# SdpSchemRev1.net
KiCad netlist of a schematic drawn in Altium Designer
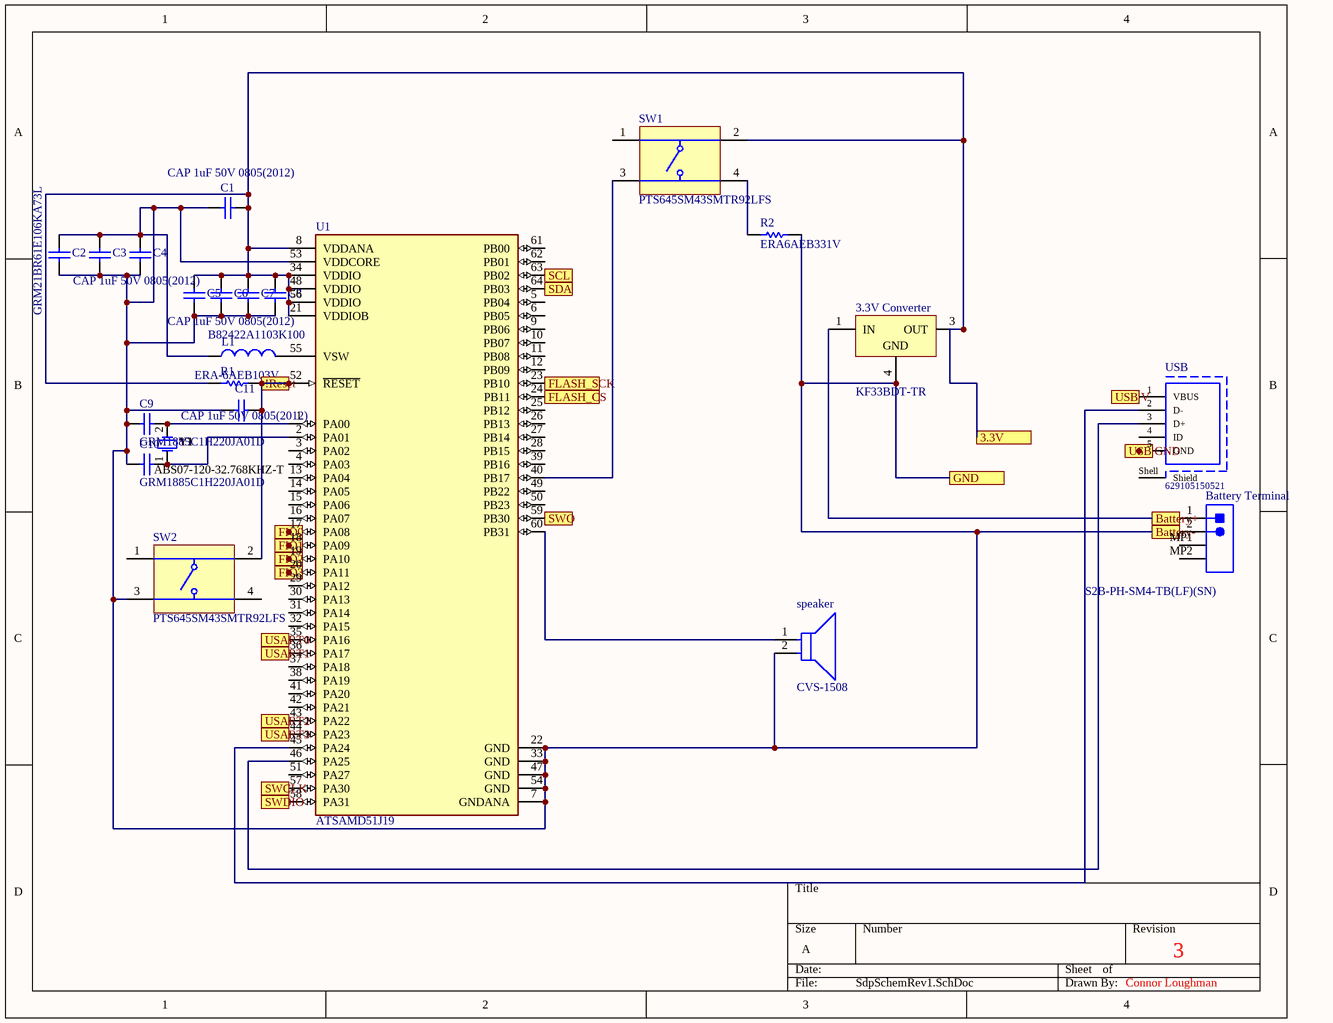
[diagram p0: SdpSchemRev1.SchDoc]

(export (version "E")
  (design (tool "Eeschema 10.0.6"))
  (components
    (comp (ref "3.3V Converter")
      (value "KF33BDT-TR")
      (footprint "TO-252_L")
      (description "Very Low Drop Voltage Regulators with Inhibit, 3.3V, 3-Pin DPAK, Tape and Reel")
      (libsource (lib "Altium Content Vault") (part "PM-REG-L4940-SOT3"))
    )
    (comp (ref "Battery Terminal")
      (value "S2B-PH-SM4-TB(LF)(SN)")
      (footprint "JST- S2B-PH-SM4-TB(LF)(SN)-2_V")
      (description "Male Header, Pitch 2 mm, 1 x 2 Position, Height 5.5 mm, -25 to 85 degC, RoHS, Tape and Reel")
      (libsource (lib "Altium Content Vault") (part "CN-1P-2M-R2"))
    )
    (comp (ref "C1")
      (value "CAP 1uF 50V 0805(2012)")
      (footprint "CAPC0805(2012)145_L")
      (description "CAP 1uF 50V ±10% 0805 (2012 Metric) Thickness 1.45mm SMD")
      (fields (field (name "TOLERANCE") "Â±10%"))
      (libsource (lib "Altium Content Vault") (part "CAP"))
    )
    (comp (ref "C2")
      (value "GRM21BR61E106KA73L")
      (footprint "CAPC2013X135X45ML10T25")
      (fields (field (name "MANUFACTURER") "Murata"))
      (libsource (lib "Altium Content Vault") (part "CAP"))
    )
    (comp (ref "C3")
      (value "~")
      (footprint "CAPC0805(2012)145_L")
      (description "CAP 1uF 50V ±10% 0805 (2012 Metric) Thickness 1.45mm SMD")
      (fields (field (name "TOLERANCE") "Â±10%"))
      (libsource (lib "Altium Content Vault") (part "CAP"))
    )
    (comp (ref "C4")
      (value "CAP 1uF 50V 0805(2012)")
      (footprint "CAPC0805(2012)145_L")
      (description "CAP 1uF 50V ±10% 0805 (2012 Metric) Thickness 1.45mm SMD")
      (fields (field (name "TOLERANCE") "Â±10%"))
      (libsource (lib "Altium Content Vault") (part "CAP"))
    )
    (comp (ref "C5")
      (value "~")
      (footprint "CAPC0805(2012)145_L")
      (description "CAP 1uF 50V ±10% 0805 (2012 Metric) Thickness 1.45mm SMD")
      (fields (field (name "TOLERANCE") "Â±10%"))
      (libsource (lib "Altium Content Vault") (part "CAP"))
    )
    (comp (ref "C6")
      (value "~")
      (footprint "CAPC0805(2012)145_L")
      (description "CAP 1uF 50V ±10% 0805 (2012 Metric) Thickness 1.45mm SMD")
      (fields (field (name "TOLERANCE") "Â±10%"))
      (libsource (lib "Altium Content Vault") (part "CAP"))
    )
    (comp (ref "C7")
      (value "~")
      (footprint "CAPC0805(2012)145_L")
      (description "CAP 1uF 50V ±10% 0805 (2012 Metric) Thickness 1.45mm SMD")
      (fields (field (name "TOLERANCE") "Â±10%"))
      (libsource (lib "Altium Content Vault") (part "CAP"))
    )
    (comp (ref "C8")
      (value "CAP 1uF 50V 0805(2012)")
      (footprint "CAPC0805(2012)145_L")
      (description "CAP 1uF 50V ±10% 0805 (2012 Metric) Thickness 1.45mm SMD")
      (fields (field (name "TOLERANCE") "Â±10%"))
      (libsource (lib "Altium Content Vault") (part "CAP"))
    )
    (comp (ref "C9")
      (value "GRM1885C1H220JA01D")
      (footprint "CAPC1608X90X35ML10T15")
      (description "Chip Capacitor, 22 pF, +/- 5%, 50 V, -55 to 125 degC, 0603 (1608 Metric), RoHS, Tape and Reel")
      (fields (field (name "MANUFACTURER") "Murata"))
      (libsource (lib "Altium Content Vault") (part "CAP-NP-2"))
    )
    (comp (ref "C10")
      (value "GRM1885C1H220JA01D")
      (footprint "CAPC1608X90X35ML10T15")
      (description "Chip Capacitor, 22 pF, +/- 5%, 50 V, -55 to 125 degC, 0603 (1608 Metric), RoHS, Tape and Reel")
      (fields (field (name "MANUFACTURER") "Murata"))
      (libsource (lib "Altium Content Vault") (part "CAP-NP-2"))
    )
    (comp (ref "C11")
      (value "CAP 1uF 50V 0805(2012)")
      (footprint "CAPC0805(2012)145_L")
      (description "CAP 1uF 50V ±10% 0805 (2012 Metric) Thickness 1.45mm SMD")
      (fields (field (name "TOLERANCE") "Â±10%"))
      (libsource (lib "Altium Content Vault") (part "CAP"))
    )
    (comp (ref "L1")
      (value "B82422A1103K100")
      (footprint "TDK-B82422A1103K100_V")
      (description "Wirewound Inductor, 10 uF, +/- 10%, 180 mA, -55 to 125 degC, 2-Pin SMD, RoHS, Tape and Reel")
      (fields (field (name "TOLERANCE") "±10%") (field (name "MANUFACTURER") "EPCOS-(TDK)"))
      (libsource (lib "Altium Content Vault") (part "IND-2"))
    )
    (comp (ref "R1")
      (value "ERA-6AEB103V")
      (footprint "RESC2013X60X40LL20T25_A")
      (fields (field (name "TOLERANCE") "0.1%") (field (name "MANUFACTURER") "Panasonic"))
      (libsource (lib "Altium Content Vault") (part "RES-2"))
    )
    (comp (ref "R2")
      (value "ERA6AEB331V")
      (footprint "RESC2013X60X40LL20T25")
      (fields (field (name "MANUFACTURER") "Panasonic"))
      (libsource (lib "Altium Content Vault") (part "RES"))
    )
    (comp (ref "speaker")
      (value "CVS-1508")
      (footprint "FP-CVS-1508-MFG")
      (description "SPEAKER 8OHM 300MW TOP PORT 87DB")
      (fields
        (field (name "MANUFACTURER") "CUI Inc")
        (field (name "OCTOPART") "https://octopart.com/cvs-1508-cui-21325683")
      )
      (libsource (lib "Altium Content Vault") (part "1973c4b650225fd2ddacaff6b763965"))
    )
    (comp (ref "SW1")
      (value "PTS645SM43SMTR92LFS")
      (footprint "ITT-PTS645S-4_V")
      (description "6 mm Tact Switche, SPST, NO, -20 to 60 degC, 4-Pin SMT, RoHS, Tape and Reel")
      (fields (field (name "MANUFACTURER") "ITT Cannon"))
      (libsource (lib "Altium Content Vault") (part "SW-SPST-4_A"))
    )
    (comp (ref "SW2")
      (value "PTS645SM43SMTR92LFS")
      (footprint "ITT-PTS645S-4_V")
      (description "6 mm Tact Switche, SPST, NO, -20 to 60 degC, 4-Pin SMT, RoHS, Tape and Reel")
      (fields (field (name "MANUFACTURER") "ITT Cannon"))
      (libsource (lib "Altium Content Vault") (part "SW-SPST-4_A"))
    )
    (comp (ref "U1")
      (value "ATSAMD51J19")
      (footprint "FP-C04-085-MFG")
      (description "IC MCU 32BIT 1MB FLASH 64TQFP")
      (fields
        (field (name "MANUFACTURER PART NUMBER") "ATSAMD51J20A-AU")
        (field (name "MANUFACTURER") "Microchip")
      )
      (libsource (lib "Altium Content Vault") (part "fef81d84dc7d39f73f4c24a268ec8e6"))
    )
    (comp (ref "USB")
      (value "629105150521")
      (footprint "629105150521")
      (description "Micro USB 2.0 Type B Receptacle WR-COM, Horizontal, SMT, with Pegs, High Current at Pin 1 & Pin 5")
      (fields (field (name "MANUFACTURER") "Wurth Elektronik") (field (name "PUBLISHER") "WurthElektronik"))
      (libsource (lib "Altium Content Vault") (part "WE-USB-5-1SHLD"))
    )
    (comp (ref "Y1")
      (value "ABS07-120-32.768KHZ-T")
      (footprint "ABRA-ABS07_A_V")
      (description "Tuning Fork Crystal, 32.768 KHz, +/- 20 ppm, -40 to 85 degC, 2-Pin SMD, RoHS, Tape and Reel")
      (fields (field (name "MANUFACTURER") "Abracon") (field (name "TOLERANCE") "20ppm"))
      (libsource (lib "Altium Content Vault") (part "XTAL-1-2-2"))
    )
  )
  (nets
    (net (code "1") (name "/!Reset") (class "Default")
      (node (ref "C11") (pin "2") (pinfunction "2_2") (pintype "passive"))
      (node (ref "R1") (pin "2") (pinfunction "2_2") (pintype "passive"))
      (node (ref "SW2") (pin "2") (pinfunction "2_2") (pintype "passive"))
      (node (ref "U1") (pin "52") (pinfunction "~{RESET}_52") (pintype "input"))
    )
    (net (code "2") (name "/3.3V") (class "Default")
      (node (ref "3.3V Converter") (pin "3") (pinfunction "OUT_3") (pintype "power_in"))
      (node (ref "C1") (pin "2") (pinfunction "2_2") (pintype "passive"))
      (node (ref "C5") (pin "2") (pinfunction "2_2") (pintype "passive"))
      (node (ref "C6") (pin "2") (pinfunction "2_2") (pintype "passive"))
      (node (ref "C7") (pin "2") (pinfunction "2_2") (pintype "passive"))
      (node (ref "C8") (pin "2") (pinfunction "2_2") (pintype "passive"))
      (node (ref "R1") (pin "1") (pinfunction "1_1") (pintype "passive"))
      (node (ref "SW1") (pin "2") (pinfunction "2_2") (pintype "passive"))
      (node (ref "U1") (pin "21") (pinfunction "VDDIOB_21") (pintype "power_in"))
      (node (ref "U1") (pin "34") (pinfunction "VDDIO_34") (pintype "power_in"))
      (node (ref "U1") (pin "48") (pinfunction "VDDIO_48") (pintype "power_in"))
      (node (ref "U1") (pin "56") (pinfunction "VDDIO_56") (pintype "power_in"))
      (node (ref "U1") (pin "8") (pinfunction "VDDANA_8") (pintype "power_in"))
    )
    (net (code "3") (name "/Battery+") (class "Default")
      (node (ref "3.3V Converter") (pin "1") (pinfunction "IN_1") (pintype "power_in"))
      (node (ref "Battery Terminal") (pin "1") (pinfunction "1_1") (pintype "passive"))
    )
    (net (code "4") (name "/Battery-") (class "Default")
      (node (ref "3.3V Converter") (pin "4") (pinfunction "GND_4") (pintype "power_in"))
      (node (ref "Battery Terminal") (pin "2") (pinfunction "2_2") (pintype "passive"))
      (node (ref "C1") (pin "1") (pinfunction "1_1") (pintype "passive"))
      (node (ref "C10") (pin "1") (pinfunction "1_1") (pintype "passive"))
      (node (ref "C11") (pin "1") (pinfunction "1_1") (pintype "passive"))
      (node (ref "C2") (pin "1") (pinfunction "1_1") (pintype "passive"))
      (node (ref "C2") (pin "2") (pinfunction "2_2") (pintype "passive"))
      (node (ref "C3") (pin "1") (pinfunction "1_1") (pintype "passive"))
      (node (ref "C3") (pin "2") (pinfunction "2_2") (pintype "passive"))
      (node (ref "C4") (pin "1") (pinfunction "1_1") (pintype "passive"))
      (node (ref "C4") (pin "2") (pinfunction "2_2") (pintype "passive"))
      (node (ref "C5") (pin "1") (pinfunction "1_1") (pintype "passive"))
      (node (ref "C6") (pin "1") (pinfunction "1_1") (pintype "passive"))
      (node (ref "C7") (pin "1") (pinfunction "1_1") (pintype "passive"))
      (node (ref "C8") (pin "1") (pinfunction "1_1") (pintype "passive"))
      (node (ref "C9") (pin "1") (pinfunction "1_1") (pintype "passive"))
      (node (ref "L1") (pin "1") (pinfunction "1_1") (pintype "passive"))
      (node (ref "R2") (pin "2") (pinfunction "2_2") (pintype "passive"))
      (node (ref "SW2") (pin "3") (pinfunction "3_3") (pintype "passive"))
      (node (ref "U1") (pin "22") (pinfunction "GND_22") (pintype "power_in"))
      (node (ref "U1") (pin "33") (pinfunction "GND_33") (pintype "power_in"))
      (node (ref "U1") (pin "47") (pinfunction "GND_47") (pintype "power_in"))
      (node (ref "U1") (pin "53") (pinfunction "VDDCORE_53") (pintype "power_in"))
      (node (ref "U1") (pin "54") (pinfunction "GND_54") (pintype "power_in"))
      (node (ref "U1") (pin "7") (pinfunction "GNDANA_7") (pintype "power_in"))
      (node (ref "speaker") (pin "2") (pinfunction "A_2") (pintype "passive"))
    )
    (net (code "9") (name "/FLASH_CS") (class "Default")
      (node (ref "U1") (pin "24") (pinfunction "PB11_24") (pintype "bidirectional"))
    )
    (net (code "10") (name "/FLASH_SCK") (class "Default")
      (node (ref "U1") (pin "23") (pinfunction "PB10_23") (pintype "bidirectional"))
    )
    (net (code "11") (name "/SCL") (class "Default")
      (node (ref "U1") (pin "63") (pinfunction "PB02_63") (pintype "bidirectional"))
    )
    (net (code "12") (name "/SDA") (class "Default")
      (node (ref "U1") (pin "64") (pinfunction "PB03_64") (pintype "bidirectional"))
    )
    (net (code "13") (name "/SWCLK") (class "Default")
      (node (ref "U1") (pin "57") (pinfunction "PA30_57") (pintype "bidirectional"))
    )
    (net (code "14") (name "/SWDIO") (class "Default")
      (node (ref "U1") (pin "58") (pinfunction "PA31_58") (pintype "bidirectional"))
    )
    (net (code "15") (name "/SWO") (class "Default")
      (node (ref "U1") (pin "59") (pinfunction "PB30_59") (pintype "bidirectional"))
    )
    (net (code "16") (name "/USART0") (class "Default")
      (node (ref "U1") (pin "35") (pinfunction "PA16_35") (pintype "bidirectional"))
    )
    (net (code "17") (name "/USART1") (class "Default")
      (node (ref "U1") (pin "36") (pinfunction "PA17_36") (pintype "bidirectional"))
    )
    (net (code "18") (name "/USART2") (class "Default")
      (node (ref "U1") (pin "43") (pinfunction "PA22_43") (pintype "bidirectional"))
    )
    (net (code "19") (name "/USART3") (class "Default")
      (node (ref "U1") (pin "44") (pinfunction "PA23_44") (pintype "bidirectional"))
    )
    (net (code "21") (name "/USB V") (class "Default")
      (node (ref "USB") (pin "1") (pinfunction "VBUS_1") (pintype "passive"))
    )
    (net (code "22") (name "Net-(R2-Pad1)") (class "Default")
      (node (ref "R2") (pin "1") (pinfunction "1_1") (pintype "passive"))
      (node (ref "SW1") (pin "4") (pinfunction "4_4") (pintype "passive"))
    )
    (net (code "23") (name "Net-(U1-PA00)") (class "Default")
      (node (ref "C9") (pin "2") (pinfunction "2_2") (pintype "passive"))
      (node (ref "U1") (pin "1") (pinfunction "PA00_1") (pintype "bidirectional"))
      (node (ref "Y1") (pin "2") (pinfunction "2_2") (pintype "passive"))
    )
    (net (code "24") (name "Net-(U1-PA01)") (class "Default")
      (node (ref "C10") (pin "2") (pinfunction "2_2") (pintype "passive"))
      (node (ref "U1") (pin "2") (pinfunction "PA01_2") (pintype "bidirectional"))
      (node (ref "Y1") (pin "1") (pinfunction "1_1") (pintype "passive"))
    )
    (net (code "25") (name "Net-(U1-PA24)") (class "Default")
      (node (ref "U1") (pin "45") (pinfunction "PA24_45") (pintype "bidirectional"))
      (node (ref "USB") (pin "2") (pinfunction "D-_2") (pintype "passive"))
    )
    (net (code "26") (name "Net-(U1-PA25)") (class "Default")
      (node (ref "U1") (pin "46") (pinfunction "PA25_46") (pintype "bidirectional"))
      (node (ref "USB") (pin "3") (pinfunction "D+_3") (pintype "passive"))
    )
    (net (code "27") (name "Net-(U1-PB17)") (class "Default")
      (node (ref "SW1") (pin "3") (pinfunction "3_3") (pintype "passive"))
      (node (ref "U1") (pin "40") (pinfunction "PB17_40") (pintype "bidirectional"))
    )
    (net (code "28") (name "Net-(U1-PB31)") (class "Default")
      (node (ref "U1") (pin "60") (pinfunction "PB31_60") (pintype "bidirectional"))
      (node (ref "speaker") (pin "1") (pinfunction "C_1") (pintype "passive"))
    )
    (net (code "29") (name "Net-(U1-VSW)") (class "Default")
      (node (ref "L1") (pin "2") (pinfunction "2_2") (pintype "passive"))
      (node (ref "U1") (pin "55") (pinfunction "VSW_55") (pintype "power_in"))
    )
    (net (code "30") (name "unconnected-(Battery Terminal-PadMP1)") (class "Default")
      (node (ref "Battery Terminal") (pin "MP1") (pinfunction "MP1_MP1") (pintype "passive"))
    )
    (net (code "31") (name "unconnected-(Battery Terminal-PadMP2)") (class "Default")
      (node (ref "Battery Terminal") (pin "MP2") (pinfunction "MP2_MP2") (pintype "passive"))
    )
    (net (code "32") (name "unconnected-(SW1-Pad1)") (class "Default")
      (node (ref "SW1") (pin "1") (pinfunction "1_1") (pintype "passive"))
    )
    (net (code "33") (name "unconnected-(SW2-Pad1)") (class "Default")
      (node (ref "SW2") (pin "1") (pinfunction "1_1") (pintype "passive"))
    )
    (net (code "34") (name "unconnected-(SW2-Pad4)") (class "Default")
      (node (ref "SW2") (pin "4") (pinfunction "4_4") (pintype "passive"))
    )
    (net (code "35") (name "unconnected-(U1-PA02-Pad3)") (class "Default")
      (node (ref "U1") (pin "3") (pinfunction "PA02_3") (pintype "bidirectional"))
    )
    (net (code "36") (name "unconnected-(U1-PA03-Pad4)") (class "Default")
      (node (ref "U1") (pin "4") (pinfunction "PA03_4") (pintype "bidirectional"))
    )
    (net (code "37") (name "unconnected-(U1-PA04-Pad13)") (class "Default")
      (node (ref "U1") (pin "13") (pinfunction "PA04_13") (pintype "bidirectional"))
    )
    (net (code "38") (name "unconnected-(U1-PA05-Pad14)") (class "Default")
      (node (ref "U1") (pin "14") (pinfunction "PA05_14") (pintype "bidirectional"))
    )
    (net (code "39") (name "unconnected-(U1-PA06-Pad15)") (class "Default")
      (node (ref "U1") (pin "15") (pinfunction "PA06_15") (pintype "bidirectional"))
    )
    (net (code "40") (name "unconnected-(U1-PA07-Pad16)") (class "Default")
      (node (ref "U1") (pin "16") (pinfunction "PA07_16") (pintype "bidirectional"))
    )
    (net (code "41") (name "unconnected-(U1-PA08-Pad17)") (class "Default")
      (node (ref "U1") (pin "17") (pinfunction "PA08_17") (pintype "bidirectional"))
    )
    (net (code "42") (name "unconnected-(U1-PA09-Pad18)") (class "Default")
      (node (ref "U1") (pin "18") (pinfunction "PA09_18") (pintype "bidirectional"))
    )
    (net (code "43") (name "unconnected-(U1-PA10-Pad19)") (class "Default")
      (node (ref "U1") (pin "19") (pinfunction "PA10_19") (pintype "bidirectional"))
    )
    (net (code "44") (name "unconnected-(U1-PA11-Pad20)") (class "Default")
      (node (ref "U1") (pin "20") (pinfunction "PA11_20") (pintype "bidirectional"))
    )
    (net (code "45") (name "unconnected-(U1-PA12-Pad29)") (class "Default")
      (node (ref "U1") (pin "29") (pinfunction "PA12_29") (pintype "bidirectional"))
    )
    (net (code "46") (name "unconnected-(U1-PA13-Pad30)") (class "Default")
      (node (ref "U1") (pin "30") (pinfunction "PA13_30") (pintype "bidirectional"))
    )
    (net (code "47") (name "unconnected-(U1-PA14-Pad31)") (class "Default")
      (node (ref "U1") (pin "31") (pinfunction "PA14_31") (pintype "bidirectional"))
    )
    (net (code "48") (name "unconnected-(U1-PA15-Pad32)") (class "Default")
      (node (ref "U1") (pin "32") (pinfunction "PA15_32") (pintype "bidirectional"))
    )
    (net (code "49") (name "unconnected-(U1-PA18-Pad37)") (class "Default")
      (node (ref "U1") (pin "37") (pinfunction "PA18_37") (pintype "bidirectional"))
    )
    (net (code "50") (name "unconnected-(U1-PA19-Pad38)") (class "Default")
      (node (ref "U1") (pin "38") (pinfunction "PA19_38") (pintype "bidirectional"))
    )
    (net (code "51") (name "unconnected-(U1-PA20-Pad41)") (class "Default")
      (node (ref "U1") (pin "41") (pinfunction "PA20_41") (pintype "bidirectional"))
    )
    (net (code "52") (name "unconnected-(U1-PA21-Pad42)") (class "Default")
      (node (ref "U1") (pin "42") (pinfunction "PA21_42") (pintype "bidirectional"))
    )
    (net (code "53") (name "unconnected-(U1-PA27-Pad51)") (class "Default")
      (node (ref "U1") (pin "51") (pinfunction "PA27_51") (pintype "bidirectional"))
    )
    (net (code "54") (name "unconnected-(U1-PB00-Pad61)") (class "Default")
      (node (ref "U1") (pin "61") (pinfunction "PB00_61") (pintype "bidirectional"))
    )
    (net (code "55") (name "unconnected-(U1-PB01-Pad62)") (class "Default")
      (node (ref "U1") (pin "62") (pinfunction "PB01_62") (pintype "bidirectional"))
    )
    (net (code "56") (name "unconnected-(U1-PB04-Pad5)") (class "Default")
      (node (ref "U1") (pin "5") (pinfunction "PB04_5") (pintype "bidirectional"))
    )
    (net (code "57") (name "unconnected-(U1-PB05-Pad6)") (class "Default")
      (node (ref "U1") (pin "6") (pinfunction "PB05_6") (pintype "bidirectional"))
    )
    (net (code "58") (name "unconnected-(U1-PB06-Pad9)") (class "Default")
      (node (ref "U1") (pin "9") (pinfunction "PB06_9") (pintype "bidirectional"))
    )
    (net (code "59") (name "unconnected-(U1-PB07-Pad10)") (class "Default")
      (node (ref "U1") (pin "10") (pinfunction "PB07_10") (pintype "bidirectional"))
    )
    (net (code "60") (name "unconnected-(U1-PB08-Pad11)") (class "Default")
      (node (ref "U1") (pin "11") (pinfunction "PB08_11") (pintype "bidirectional"))
    )
    (net (code "61") (name "unconnected-(U1-PB09-Pad12)") (class "Default")
      (node (ref "U1") (pin "12") (pinfunction "PB09_12") (pintype "bidirectional"))
    )
    (net (code "62") (name "unconnected-(U1-PB12-Pad25)") (class "Default")
      (node (ref "U1") (pin "25") (pinfunction "PB12_25") (pintype "bidirectional"))
    )
    (net (code "63") (name "unconnected-(U1-PB13-Pad26)") (class "Default")
      (node (ref "U1") (pin "26") (pinfunction "PB13_26") (pintype "bidirectional"))
    )
    (net (code "64") (name "unconnected-(U1-PB14-Pad27)") (class "Default")
      (node (ref "U1") (pin "27") (pinfunction "PB14_27") (pintype "bidirectional"))
    )
    (net (code "65") (name "unconnected-(U1-PB15-Pad28)") (class "Default")
      (node (ref "U1") (pin "28") (pinfunction "PB15_28") (pintype "bidirectional"))
    )
    (net (code "66") (name "unconnected-(U1-PB16-Pad39)") (class "Default")
      (node (ref "U1") (pin "39") (pinfunction "PB16_39") (pintype "bidirectional"))
    )
    (net (code "67") (name "unconnected-(U1-PB22-Pad49)") (class "Default")
      (node (ref "U1") (pin "49") (pinfunction "PB22_49") (pintype "bidirectional"))
    )
    (net (code "68") (name "unconnected-(U1-PB23-Pad50)") (class "Default")
      (node (ref "U1") (pin "50") (pinfunction "PB23_50") (pintype "bidirectional"))
    )
    (net (code "69") (name "unconnected-(USB-GND-Pad5)") (class "Default")
      (node (ref "USB") (pin "5") (pinfunction "GND_5") (pintype "passive"))
    )
    (net (code "70") (name "unconnected-(USB-ID-Pad4)") (class "Default")
      (node (ref "USB") (pin "4") (pinfunction "ID_4") (pintype "passive"))
    )
    (net (code "71") (name "unconnected-(USB-Shield-PadShell)") (class "Default")
      (node (ref "USB") (pin "Shell") (pinfunction "Shield_Shell") (pintype "passive"))
    )
  )
)
